# Mixer.net
KiCad netlist of a schematic drawn in Altium Designer
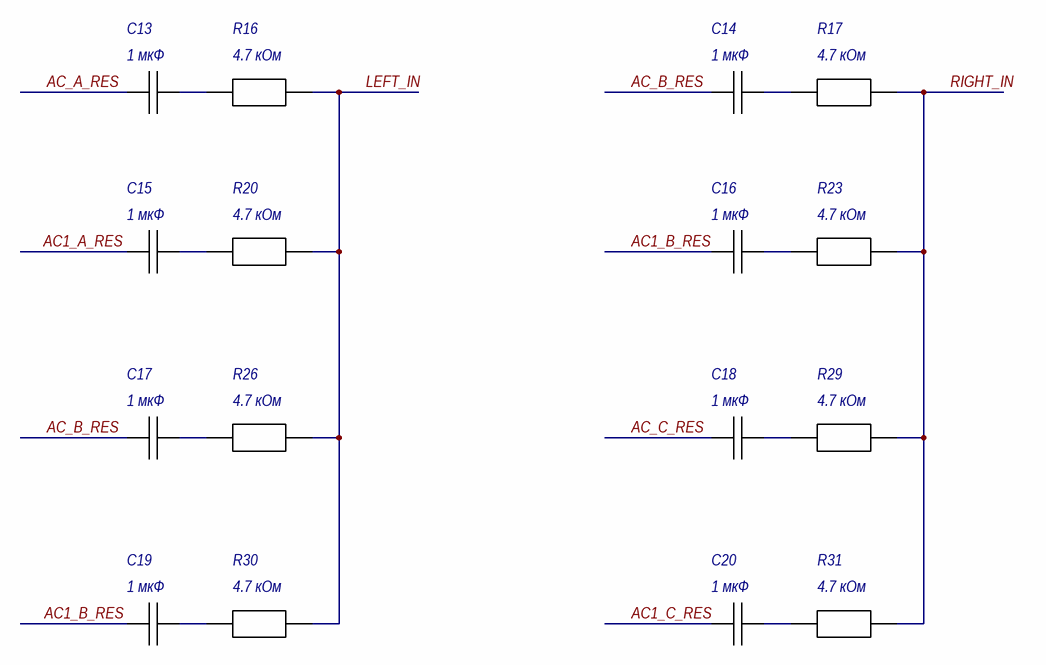
[diagram p0: Mixer.SchDoc]

(export (version "E")
  (design (tool "Eeschema 10.0.6"))
  (components
    (comp (ref "C13")
      (value "1 мкФ")
      (footprint "C 1206")
      (description "SMD Capacitor 1206")
      (fields
        (field (name "TOLERANCE") "/Укажите допуск в процентах/")
        (field (name "MANUFACTURER") "/Укажите компанию-производителя/")
      )
      (libsource (lib "my_lib") (part "CAP 1206"))
    )
    (comp (ref "C14")
      (value "1 мкФ")
      (footprint "C 1206")
      (description "SMD Capacitor 1206")
      (fields
        (field (name "TOLERANCE") "/Укажите допуск в процентах/")
        (field (name "MANUFACTURER") "/Укажите компанию-производителя/")
      )
      (libsource (lib "my_lib") (part "CAP 1206"))
    )
    (comp (ref "C15")
      (value "1 мкФ")
      (footprint "C 1206")
      (description "SMD Capacitor 1206")
      (fields
        (field (name "TOLERANCE") "/Укажите допуск в процентах/")
        (field (name "MANUFACTURER") "/Укажите компанию-производителя/")
      )
      (libsource (lib "my_lib") (part "CAP 1206"))
    )
    (comp (ref "C16")
      (value "1 мкФ")
      (footprint "C 1206")
      (description "SMD Capacitor 1206")
      (fields
        (field (name "TOLERANCE") "/Укажите допуск в процентах/")
        (field (name "MANUFACTURER") "/Укажите компанию-производителя/")
      )
      (libsource (lib "my_lib") (part "CAP 1206"))
    )
    (comp (ref "C17")
      (value "1 мкФ")
      (footprint "C 1206")
      (description "SMD Capacitor 1206")
      (fields
        (field (name "TOLERANCE") "/Укажите допуск в процентах/")
        (field (name "MANUFACTURER") "/Укажите компанию-производителя/")
      )
      (libsource (lib "my_lib") (part "CAP 1206"))
    )
    (comp (ref "C18")
      (value "1 мкФ")
      (footprint "C 1206")
      (description "SMD Capacitor 1206")
      (fields
        (field (name "TOLERANCE") "/Укажите допуск в процентах/")
        (field (name "MANUFACTURER") "/Укажите компанию-производителя/")
      )
      (libsource (lib "my_lib") (part "CAP 1206"))
    )
    (comp (ref "C19")
      (value "1 мкФ")
      (footprint "C 1206")
      (description "SMD Capacitor 1206")
      (fields
        (field (name "TOLERANCE") "/Укажите допуск в процентах/")
        (field (name "MANUFACTURER") "/Укажите компанию-производителя/")
      )
      (libsource (lib "my_lib") (part "CAP 1206"))
    )
    (comp (ref "C20")
      (value "1 мкФ")
      (footprint "C 1206")
      (description "SMD Capacitor 1206")
      (fields
        (field (name "TOLERANCE") "/Укажите допуск в процентах/")
        (field (name "MANUFACTURER") "/Укажите компанию-производителя/")
      )
      (libsource (lib "my_lib") (part "CAP 1206"))
    )
    (comp (ref "R16") (value "4.7 кОм") (footprint "RES 0805") (libsource (lib "my_lib") (part "RES 0805")))
    (comp (ref "R17") (value "4.7 кОм") (footprint "RES 0805") (libsource (lib "my_lib") (part "RES 0805")))
    (comp (ref "R20") (value "4.7 кОм") (footprint "RES 0805") (libsource (lib "my_lib") (part "RES 0805")))
    (comp (ref "R23") (value "4.7 кОм") (footprint "RES 0805") (libsource (lib "my_lib") (part "RES 0805")))
    (comp (ref "R26") (value "4.7 кОм") (footprint "RES 0805") (libsource (lib "my_lib") (part "RES 0805")))
    (comp (ref "R29") (value "4.7 кОм") (footprint "RES 0805") (libsource (lib "my_lib") (part "RES 0805")))
    (comp (ref "R30") (value "4.7 кОм") (footprint "RES 0805") (libsource (lib "my_lib") (part "RES 0805")))
    (comp (ref "R31") (value "4.7 кОм") (footprint "RES 0805") (libsource (lib "my_lib") (part "RES 0805")))
  )
  (nets
    (net (code "1") (name "/AC1_A_RES") (class "Default")
      (node (ref "C15") (pin "1") (pinfunction "1_1") (pintype "passive"))
    )
    (net (code "2") (name "/AC1_B_RES") (class "Default")
      (node (ref "C16") (pin "1") (pinfunction "1_1") (pintype "passive"))
      (node (ref "C19") (pin "1") (pinfunction "1_1") (pintype "passive"))
    )
    (net (code "3") (name "/AC1_C_RES") (class "Default")
      (node (ref "C20") (pin "1") (pinfunction "1_1") (pintype "passive"))
    )
    (net (code "4") (name "/AC_A_RES") (class "Default")
      (node (ref "C13") (pin "1") (pinfunction "1_1") (pintype "passive"))
    )
    (net (code "5") (name "/AC_B_RES") (class "Default")
      (node (ref "C14") (pin "1") (pinfunction "1_1") (pintype "passive"))
      (node (ref "C17") (pin "1") (pinfunction "1_1") (pintype "passive"))
    )
    (net (code "6") (name "/AC_C_RES") (class "Default")
      (node (ref "C18") (pin "1") (pinfunction "1_1") (pintype "passive"))
    )
    (net (code "7") (name "/LEFT_IN") (class "Default")
      (node (ref "R16") (pin "2") (pinfunction "2_2") (pintype "passive"))
      (node (ref "R20") (pin "2") (pinfunction "2_2") (pintype "passive"))
      (node (ref "R26") (pin "2") (pinfunction "2_2") (pintype "passive"))
      (node (ref "R30") (pin "2") (pinfunction "2_2") (pintype "passive"))
    )
    (net (code "8") (name "/RIGHT_IN") (class "Default")
      (node (ref "R17") (pin "2") (pinfunction "2_2") (pintype "passive"))
      (node (ref "R23") (pin "2") (pinfunction "2_2") (pintype "passive"))
      (node (ref "R29") (pin "2") (pinfunction "2_2") (pintype "passive"))
      (node (ref "R31") (pin "2") (pinfunction "2_2") (pintype "passive"))
    )
    (net (code "9") (name "Net-(C13-Pad2)") (class "Default")
      (node (ref "C13") (pin "2") (pinfunction "2_2") (pintype "passive"))
      (node (ref "R16") (pin "1") (pinfunction "1_1") (pintype "passive"))
    )
    (net (code "10") (name "Net-(C14-Pad2)") (class "Default")
      (node (ref "C14") (pin "2") (pinfunction "2_2") (pintype "passive"))
      (node (ref "R17") (pin "1") (pinfunction "1_1") (pintype "passive"))
    )
    (net (code "11") (name "Net-(C15-Pad2)") (class "Default")
      (node (ref "C15") (pin "2") (pinfunction "2_2") (pintype "passive"))
      (node (ref "R20") (pin "1") (pinfunction "1_1") (pintype "passive"))
    )
    (net (code "12") (name "Net-(C16-Pad2)") (class "Default")
      (node (ref "C16") (pin "2") (pinfunction "2_2") (pintype "passive"))
      (node (ref "R23") (pin "1") (pinfunction "1_1") (pintype "passive"))
    )
    (net (code "13") (name "Net-(C17-Pad2)") (class "Default")
      (node (ref "C17") (pin "2") (pinfunction "2_2") (pintype "passive"))
      (node (ref "R26") (pin "1") (pinfunction "1_1") (pintype "passive"))
    )
    (net (code "14") (name "Net-(C18-Pad2)") (class "Default")
      (node (ref "C18") (pin "2") (pinfunction "2_2") (pintype "passive"))
      (node (ref "R29") (pin "1") (pinfunction "1_1") (pintype "passive"))
    )
    (net (code "15") (name "Net-(C19-Pad2)") (class "Default")
      (node (ref "C19") (pin "2") (pinfunction "2_2") (pintype "passive"))
      (node (ref "R30") (pin "1") (pinfunction "1_1") (pintype "passive"))
    )
    (net (code "16") (name "Net-(C20-Pad2)") (class "Default")
      (node (ref "C20") (pin "2") (pinfunction "2_2") (pintype "passive"))
      (node (ref "R31") (pin "1") (pinfunction "1_1") (pintype "passive"))
    )
  )
)
